# contactor_feedback.net
KiCad netlist of a schematic drawn in Altium Designer
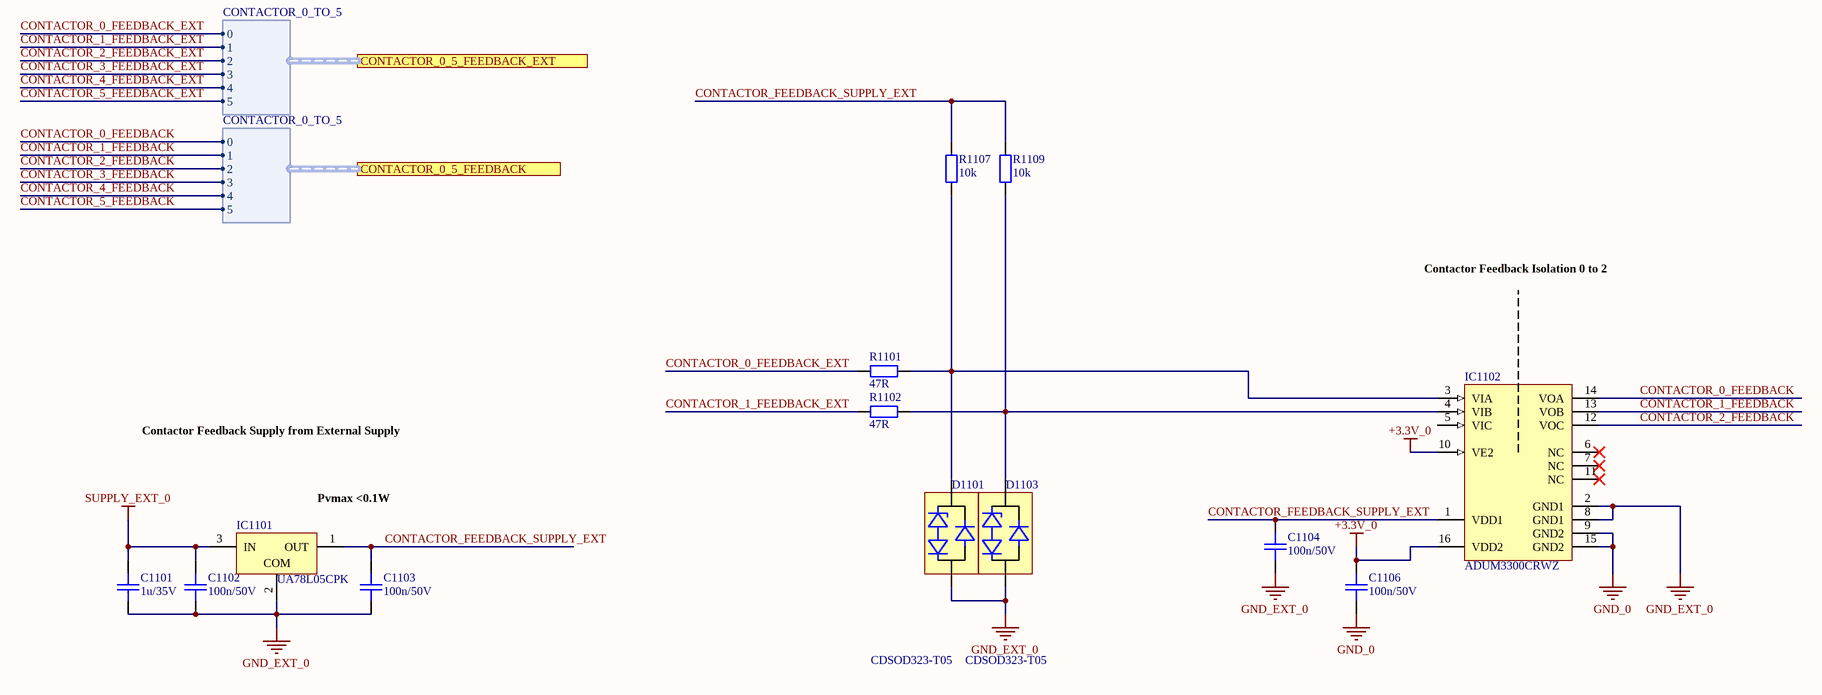
[diagram p0: contactor_feedback.SchDoc]

(export (version "E")
  (design (tool "Eeschema 10.0.6"))
  (components
    (comp (ref "C1101")
      (value "1u/35V")
      (footprint "CAPC1608X08N")
      (description "MLCC")
      (fields (field (name "PART NUMBER") "gen_C_ceramic_1u_35V_X7R_0603"))
      (libsource (lib "OE750") (part "C"))
    )
    (comp (ref "C1102")
      (value "100n/50V")
      (footprint "CAPC1608X08N")
      (description "MLCC")
      (fields (field (name "PART NUMBER") "gen_C_ceramic_100n_50V_X7R_0603"))
      (libsource (lib "OE750") (part "C"))
    )
    (comp (ref "C1103")
      (value "100n/50V")
      (footprint "CAPC1608X08N")
      (description "MLCC")
      (fields (field (name "PART NUMBER") "gen_C_ceramic_100n_50V_X7R_0603"))
      (libsource (lib "OE750") (part "C"))
    )
    (comp (ref "C1104")
      (value "100n/50V")
      (footprint "CAPC1608X08N")
      (description "MLCC")
      (fields (field (name "PART NUMBER") "gen_C_ceramic_100n_50V_X7R_0603"))
      (libsource (lib "OE750") (part "C"))
    )
    (comp (ref "C1106")
      (value "100n/50V")
      (footprint "CAPC1608X08N")
      (description "MLCC")
      (fields (field (name "PART NUMBER") "gen_C_ceramic_100n_50V_X7R_0603"))
      (libsource (lib "OE750") (part "C"))
    )
    (comp (ref "D1101")
      (value "CDSOD323-T05")
      (footprint "SODFL250X110-2N")
      (description "TVS Diode, CDSOD323 Series, Unidirectional, 5 V, 18.3 V, SOD-323, 2 Pins")
      (fields (field (name "MANUFACTURER") "Bourns"))
      (libsource (lib "OE750") (part "D_TVS_uni"))
    )
    (comp (ref "D1103")
      (value "CDSOD323-T05")
      (footprint "SODFL250X110-2N")
      (description "TVS Diode, CDSOD323 Series, Unidirectional, 5 V, 18.3 V, SOD-323, 2 Pins")
      (fields (field (name "MANUFACTURER") "Bourns"))
      (libsource (lib "OE750") (part "D_TVS_uni"))
    )
    (comp (ref "IC1101")
      (value "UA78L05CPK")
      (footprint "PK0003A_L")
      (fields (field (name "MANUFACTURER") "TexasInstruments"))
      (libsource (lib "Altium Content Vault") (part "TI-UA78L05-PK-3"))
    )
    (comp (ref "IC1102")
      (value "ADUM3300CRWZ")
      (footprint "ADI-RW-16_L")
      (fields (field (name "MANUFACTURER") "Analog Devices"))
      (libsource (lib "Altium Content Vault") (part "ADI-ADUMX300-RW-16"))
    )
    (comp (ref "R1101")
      (value "47R")
      (footprint "RESC1608X05N")
      (description "SMD Resistor 47R 0603")
      (fields (field (name "PART NUMBER") "gen_R_47R_0603") (field (name "TOLERANCE") "1%"))
      (libsource (lib "OE750") (part "R"))
    )
    (comp (ref "R1102")
      (value "47R")
      (footprint "RESC1608X05N")
      (description "SMD Resistor 47R 0603")
      (fields (field (name "PART NUMBER") "gen_R_47R_0603") (field (name "TOLERANCE") "1%"))
      (libsource (lib "OE750") (part "R"))
    )
    (comp (ref "R1107")
      (value "10k")
      (footprint "RESC1608X05N")
      (description "SMD Resistor 10k 0603")
      (fields (field (name "PART NUMBER") "gen_R_10k_0603") (field (name "TOLERANCE") "1%"))
      (libsource (lib "OE750") (part "R"))
    )
    (comp (ref "R1109")
      (value "10k")
      (footprint "RESC1608X05N")
      (description "SMD Resistor 10k 0603")
      (fields (field (name "PART NUMBER") "gen_R_10k_0603") (field (name "TOLERANCE") "1%"))
      (libsource (lib "OE750") (part "R"))
    )
  )
  (nets
    (net (code "2") (name "+3.3V_0") (class "Default")
      (node (ref "C1106") (pin "1") (pinfunction "1_1") (pintype "passive"))
      (node (ref "IC1102") (pin "10") (pinfunction "VE2_10") (pintype "input"))
      (node (ref "IC1102") (pin "16") (pinfunction "VDD2_16") (pintype "power_in"))
    )
    (net (code "3") (name "/CONTACTOR_0_FEEDBACK") (class "Default")
      (node (ref "IC1102") (pin "14") (pinfunction "VOA_14") (pintype "tri_state"))
    )
    (net (code "4") (name "/CONTACTOR_0_FEEDBACK_EXT") (class "Default")
      (node (ref "R1101") (pin "1") (pinfunction "1_1") (pintype "passive"))
    )
    (net (code "5") (name "/CONTACTOR_1_FEEDBACK") (class "Default")
      (node (ref "IC1102") (pin "13") (pinfunction "VOB_13") (pintype "tri_state"))
    )
    (net (code "6") (name "/CONTACTOR_1_FEEDBACK_EXT") (class "Default")
      (node (ref "R1102") (pin "1") (pinfunction "1_1") (pintype "passive"))
    )
    (net (code "7") (name "/CONTACTOR_2_FEEDBACK") (class "Default")
      (node (ref "IC1102") (pin "12") (pinfunction "VOC_12") (pintype "tri_state"))
    )
    (net (code "15") (name "/CONTACTOR_FEEDBACK_SUPPLY_EXT") (class "Default")
      (node (ref "C1103") (pin "1") (pinfunction "1_1") (pintype "passive"))
      (node (ref "C1104") (pin "1") (pinfunction "1_1") (pintype "passive"))
      (node (ref "IC1101") (pin "1") (pinfunction "OUT_1") (pintype "power_in"))
      (node (ref "IC1102") (pin "1") (pinfunction "VDD1_1") (pintype "power_in"))
      (node (ref "R1107") (pin "2") (pinfunction "2_2") (pintype "passive"))
      (node (ref "R1109") (pin "2") (pinfunction "2_2") (pintype "passive"))
    )
    (net (code "17") (name "GND_0") (class "Default")
      (node (ref "C1106") (pin "2") (pinfunction "2_2") (pintype "passive"))
      (node (ref "IC1102") (pin "15") (pinfunction "GND2_15") (pintype "power_in"))
      (node (ref "IC1102") (pin "9") (pinfunction "GND2_9") (pintype "power_in"))
    )
    (net (code "18") (name "GND_EXT_0") (class "Default")
      (node (ref "C1101") (pin "2") (pinfunction "2_2") (pintype "passive"))
      (node (ref "C1102") (pin "2") (pinfunction "2_2") (pintype "passive"))
      (node (ref "C1103") (pin "2") (pinfunction "2_2") (pintype "passive"))
      (node (ref "C1104") (pin "2") (pinfunction "2_2") (pintype "passive"))
      (node (ref "D1101") (pin "2") (pinfunction "A_2") (pintype "passive"))
      (node (ref "D1103") (pin "2") (pinfunction "A_2") (pintype "passive"))
      (node (ref "IC1101") (pin "2") (pinfunction "COM_2") (pintype "power_in"))
      (node (ref "IC1102") (pin "2") (pinfunction "GND1_2") (pintype "power_in"))
      (node (ref "IC1102") (pin "8") (pinfunction "GND1_8") (pintype "power_in"))
    )
    (net (code "19") (name "Net-(D1101-K)") (class "Default")
      (node (ref "D1101") (pin "1") (pinfunction "K_1") (pintype "passive"))
      (node (ref "IC1102") (pin "3") (pinfunction "VIA_3") (pintype "input"))
      (node (ref "R1101") (pin "2") (pinfunction "2_2") (pintype "passive"))
      (node (ref "R1107") (pin "1") (pinfunction "1_1") (pintype "passive"))
    )
    (net (code "20") (name "Net-(D1103-K)") (class "Default")
      (node (ref "D1103") (pin "1") (pinfunction "K_1") (pintype "passive"))
      (node (ref "IC1102") (pin "4") (pinfunction "VIB_4") (pintype "input"))
      (node (ref "R1102") (pin "2") (pinfunction "2_2") (pintype "passive"))
      (node (ref "R1109") (pin "1") (pinfunction "1_1") (pintype "passive"))
    )
    (net (code "21") (name "SUPPLY_EXT_0") (class "Default")
      (node (ref "C1101") (pin "1") (pinfunction "1_1") (pintype "passive"))
      (node (ref "C1102") (pin "1") (pinfunction "1_1") (pintype "passive"))
      (node (ref "IC1101") (pin "3") (pinfunction "IN_3") (pintype "power_in"))
    )
    (net (code "22") (name "unconnected-(IC1102-NC-Pad6)") (class "Default")
      (node (ref "IC1102") (pin "6") (pinfunction "NC_6") (pintype "passive+no_connect"))
    )
    (net (code "23") (name "unconnected-(IC1102-NC-Pad7)") (class "Default")
      (node (ref "IC1102") (pin "7") (pinfunction "NC_7") (pintype "passive+no_connect"))
    )
    (net (code "24") (name "unconnected-(IC1102-NC-Pad11)") (class "Default")
      (node (ref "IC1102") (pin "11") (pinfunction "NC_11") (pintype "passive+no_connect"))
    )
    (net (code "25") (name "unconnected-(IC1102-VIC-Pad5)") (class "Default")
      (node (ref "IC1102") (pin "5") (pinfunction "VIC_5") (pintype "input"))
    )
  )
)
